# RamaTAV1.net
KiCad netlist of a schematic drawn in EAGLE
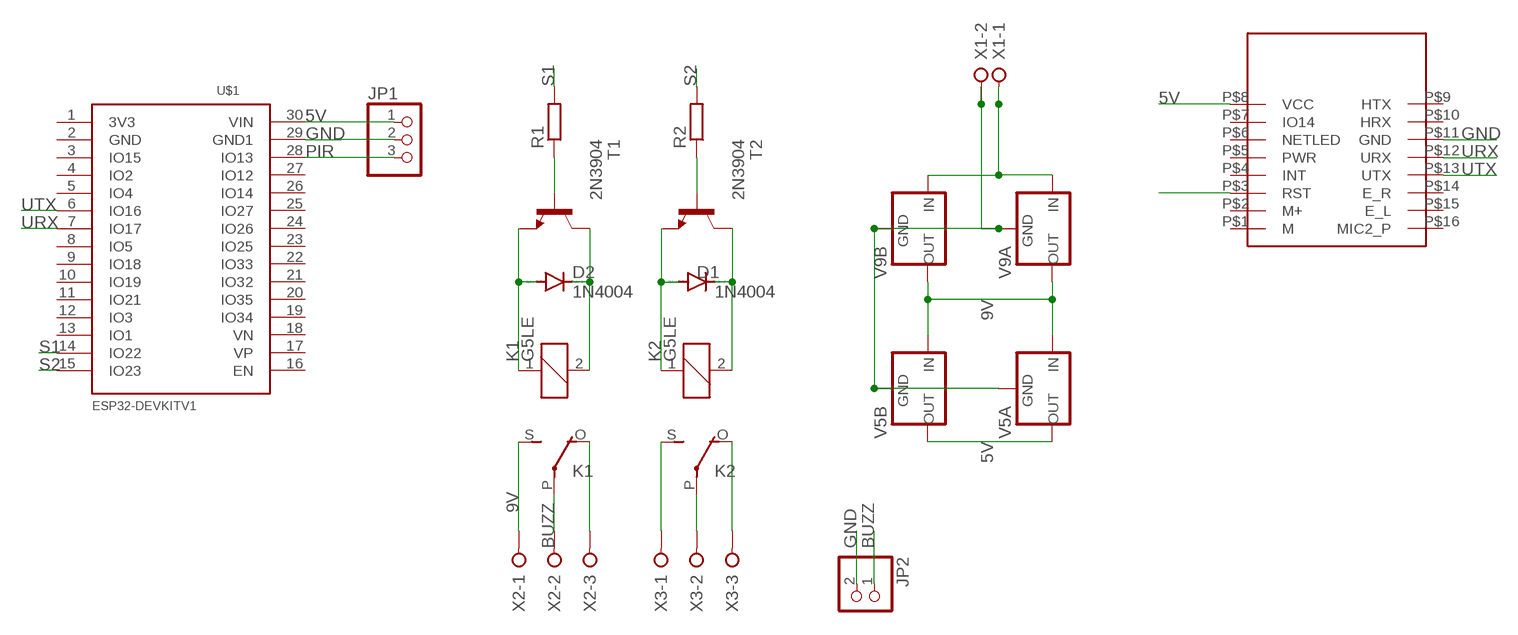
[diagram p0: schematic, sheet 1]

(export (version "E")
  (design (tool "Eeschema 10.0.6"))
  (components
    (comp (ref "D1")
      (value "1N4004")
      (footprint "eagle-import:DO41-10")
      (libsource (lib "eagle-import") (part "1N4004"))
    )
    (comp (ref "D2")
      (value "1N4004")
      (footprint "eagle-import:DO41-10")
      (libsource (lib "eagle-import") (part "1N4004"))
    )
    (comp (ref "JP1")
      (value "PINHD-1X3")
      (footprint "eagle-import:1X03")
      (libsource (lib "eagle-import") (part "PINHD-1X3"))
    )
    (comp (ref "JP2")
      (value "PINHD-1X2")
      (footprint "eagle-import:1X02")
      (libsource (lib "eagle-import") (part "PINHD-1X2"))
    )
    (comp (ref "K1")
      (value "G5LE")
      (footprint "eagle-import:G5LE")
      (libsource (lib "eagle-import") (part "G5LE"))
    )
    (comp (ref "K2")
      (value "G5LE")
      (footprint "eagle-import:G5LE")
      (libsource (lib "eagle-import") (part "G5LE"))
    )
    (comp (ref "R1")
      (value "R-EU_0207/10")
      (footprint "eagle-import:0207_10")
      (libsource (lib "eagle-import") (part "R-EU_0207/10"))
    )
    (comp (ref "R2")
      (value "R-EU_0207/10")
      (footprint "eagle-import:0207_10")
      (libsource (lib "eagle-import") (part "R-EU_0207/10"))
    )
    (comp (ref "T1")
      (value "2N3904")
      (footprint "eagle-import:TO92")
      (libsource (lib "eagle-import") (part "2N3904"))
    )
    (comp (ref "T2")
      (value "2N3904")
      (footprint "eagle-import:TO92")
      (libsource (lib "eagle-import") (part "2N3904"))
    )
    (comp (ref "U$1")
      (value "ESP32DEVKITV1")
      (footprint "eagle-import:ESP32-DEVKITV1")
      (libsource (lib "eagle-import") (part "ESP32DEVKITV1"))
    )
    (comp (ref "U$7")
      (value "SIM_A6SIM_GA6")
      (footprint "eagle-import:SIM_GA6")
      (libsource (lib "eagle-import") (part "SIM_A6SIM_GA6"))
    )
    (comp (ref "V5A")
      (value "78XXS")
      (footprint "eagle-import:78XXS")
      (libsource (lib "eagle-import") (part "78XXS"))
    )
    (comp (ref "V5B")
      (value "78XXS")
      (footprint "eagle-import:78XXS")
      (libsource (lib "eagle-import") (part "78XXS"))
    )
    (comp (ref "V9A")
      (value "78XXS")
      (footprint "eagle-import:78XXS")
      (libsource (lib "eagle-import") (part "78XXS"))
    )
    (comp (ref "V9B")
      (value "78XXS")
      (footprint "eagle-import:78XXS")
      (libsource (lib "eagle-import") (part "78XXS"))
    )
    (comp (ref "X1")
      (value "W237-02P")
      (footprint "eagle-import:W237-2")
      (libsource (lib "eagle-import") (part "W237-02P"))
    )
    (comp (ref "X2")
      (value "W237-03P")
      (footprint "eagle-import:W237-3")
      (libsource (lib "eagle-import") (part "W237-03P"))
    )
    (comp (ref "X3")
      (value "W237-03P")
      (footprint "eagle-import:W237-3")
      (libsource (lib "eagle-import") (part "W237-03P"))
    )
  )
  (nets
    (net (code "1") (name "/5V") (class "Default")
      (node (ref "JP1") (pin "1") (pinfunction "1_1") (pintype "passive"))
      (node (ref "U$1") (pin "30") (pinfunction "VIN_30") (pintype "bidirectional"))
      (node (ref "U$7") (pin "P$8") (pinfunction "VCC_P$8") (pintype "bidirectional"))
      (node (ref "V5A") (pin "OUT") (pinfunction "OUT_OUT") (pintype "passive"))
      (node (ref "V5B") (pin "OUT") (pinfunction "OUT_OUT") (pintype "passive"))
    )
    (net (code "2") (name "/9V") (class "Default")
      (node (ref "K1") (pin "S") (pinfunction "S_S") (pintype "passive"))
      (node (ref "V5A") (pin "IN") (pinfunction "IN_IN") (pintype "input"))
      (node (ref "V5B") (pin "IN") (pinfunction "IN_IN") (pintype "input"))
      (node (ref "V9A") (pin "OUT") (pinfunction "OUT_OUT") (pintype "passive"))
      (node (ref "V9B") (pin "OUT") (pinfunction "OUT_OUT") (pintype "passive"))
      (node (ref "X2") (pin "1") (pinfunction "KL_1") (pintype "passive"))
    )
    (net (code "3") (name "/BUZZ") (class "Default")
      (node (ref "JP2") (pin "1") (pinfunction "1_1") (pintype "passive"))
      (node (ref "K1") (pin "P") (pinfunction "P_P") (pintype "passive"))
      (node (ref "X2") (pin "2") (pinfunction "KL_2") (pintype "passive"))
    )
    (net (code "4") (name "/GND") (class "Default")
      (node (ref "JP1") (pin "2") (pinfunction "2_2") (pintype "passive"))
      (node (ref "JP2") (pin "2") (pinfunction "2_2") (pintype "passive"))
      (node (ref "U$1") (pin "29") (pinfunction "GND1_29") (pintype "bidirectional"))
      (node (ref "U$7") (pin "P$11") (pinfunction "GND_P$11") (pintype "bidirectional"))
    )
    (net (code "5") (name "/PIR") (class "Default")
      (node (ref "JP1") (pin "3") (pinfunction "3_3") (pintype "passive"))
      (node (ref "U$1") (pin "28") (pinfunction "IO13_28") (pintype "bidirectional"))
    )
    (net (code "6") (name "/S1") (class "Default")
      (node (ref "R1") (pin "2") (pinfunction "2_2") (pintype "passive"))
      (node (ref "U$1") (pin "14") (pinfunction "IO22_14") (pintype "bidirectional"))
    )
    (net (code "7") (name "/S2") (class "Default")
      (node (ref "R2") (pin "2") (pinfunction "2_2") (pintype "passive"))
      (node (ref "U$1") (pin "15") (pinfunction "IO23_15") (pintype "bidirectional"))
    )
    (net (code "8") (name "/URX") (class "Default")
      (node (ref "U$1") (pin "7") (pinfunction "IO17_7") (pintype "bidirectional"))
      (node (ref "U$7") (pin "P$12") (pinfunction "URX_P$12") (pintype "bidirectional"))
    )
    (net (code "9") (name "/UTX") (class "Default")
      (node (ref "U$1") (pin "6") (pinfunction "IO16_6") (pintype "bidirectional"))
      (node (ref "U$7") (pin "P$13") (pinfunction "UTX_P$13") (pintype "bidirectional"))
    )
    (net (code "10") (name "Net-(T1-B)") (class "Default")
      (node (ref "R1") (pin "1") (pinfunction "1_1") (pintype "passive"))
      (node (ref "T1") (pin "2") (pinfunction "B_2") (pintype "passive"))
    )
    (net (code "11") (name "Net-(T1-C)") (class "Default")
      (node (ref "D2") (pin "C") (pinfunction "C_C") (pintype "passive"))
      (node (ref "K1") (pin "2") (pinfunction "2_2") (pintype "passive"))
      (node (ref "T1") (pin "1") (pinfunction "C_1") (pintype "passive"))
    )
    (net (code "12") (name "Net-(T1-E)") (class "Default")
      (node (ref "D2") (pin "A") (pinfunction "A_A") (pintype "passive"))
      (node (ref "K1") (pin "1") (pinfunction "1_1") (pintype "passive"))
      (node (ref "T1") (pin "3") (pinfunction "E_3") (pintype "passive"))
    )
    (net (code "13") (name "Net-(T2-B)") (class "Default")
      (node (ref "R2") (pin "1") (pinfunction "1_1") (pintype "passive"))
      (node (ref "T2") (pin "2") (pinfunction "B_2") (pintype "passive"))
    )
    (net (code "14") (name "Net-(T2-C)") (class "Default")
      (node (ref "D1") (pin "C") (pinfunction "C_C") (pintype "passive"))
      (node (ref "K2") (pin "2") (pinfunction "2_2") (pintype "passive"))
      (node (ref "T2") (pin "1") (pinfunction "C_1") (pintype "passive"))
    )
    (net (code "15") (name "Net-(T2-E)") (class "Default")
      (node (ref "D1") (pin "A") (pinfunction "A_A") (pintype "passive"))
      (node (ref "K2") (pin "1") (pinfunction "1_1") (pintype "passive"))
      (node (ref "T2") (pin "3") (pinfunction "E_3") (pintype "passive"))
    )
    (net (code "16") (name "Net-(X1A-KL)") (class "Default")
      (node (ref "V9A") (pin "IN") (pinfunction "IN_IN") (pintype "input"))
      (node (ref "V9B") (pin "IN") (pinfunction "IN_IN") (pintype "input"))
      (node (ref "X1") (pin "1") (pinfunction "KL_1") (pintype "passive"))
    )
    (net (code "17") (name "Net-(X1B-KL)") (class "Default")
      (node (ref "V5A") (pin "GND") (pinfunction "GND_GND") (pintype "input"))
      (node (ref "V5B") (pin "GND") (pinfunction "GND_GND") (pintype "input"))
      (node (ref "V9A") (pin "GND") (pinfunction "GND_GND") (pintype "input"))
      (node (ref "V9B") (pin "GND") (pinfunction "GND_GND") (pintype "input"))
      (node (ref "X1") (pin "2") (pinfunction "KL_2") (pintype "passive"))
    )
    (net (code "18") (name "Net-(X2C-KL)") (class "Default")
      (node (ref "K1") (pin "O") (pinfunction "O_O") (pintype "passive"))
      (node (ref "X2") (pin "3") (pinfunction "KL_3") (pintype "passive"))
    )
    (net (code "19") (name "Net-(X3A-KL)") (class "Default")
      (node (ref "K2") (pin "S") (pinfunction "S_S") (pintype "passive"))
      (node (ref "X3") (pin "1") (pinfunction "KL_1") (pintype "passive"))
    )
    (net (code "20") (name "Net-(X3B-KL)") (class "Default")
      (node (ref "K2") (pin "P") (pinfunction "P_P") (pintype "passive"))
      (node (ref "X3") (pin "2") (pinfunction "KL_2") (pintype "passive"))
    )
    (net (code "21") (name "Net-(X3C-KL)") (class "Default")
      (node (ref "K2") (pin "O") (pinfunction "O_O") (pintype "passive"))
      (node (ref "X3") (pin "3") (pinfunction "KL_3") (pintype "passive"))
    )
    (net (code "22") (name "unconnected-(U$1-3V3-Pad1)") (class "Default")
      (node (ref "U$1") (pin "1") (pinfunction "3V3_1") (pintype "bidirectional"))
    )
    (net (code "23") (name "unconnected-(U$1-EN-Pad16)") (class "Default")
      (node (ref "U$1") (pin "16") (pinfunction "EN_16") (pintype "bidirectional"))
    )
    (net (code "24") (name "unconnected-(U$1-GND-Pad2)") (class "Default")
      (node (ref "U$1") (pin "2") (pinfunction "GND_2") (pintype "bidirectional"))
    )
    (net (code "25") (name "unconnected-(U$1-IO1-Pad13)") (class "Default")
      (node (ref "U$1") (pin "13") (pinfunction "IO1_13") (pintype "bidirectional"))
    )
    (net (code "26") (name "unconnected-(U$1-IO2-Pad4)") (class "Default")
      (node (ref "U$1") (pin "4") (pinfunction "IO2_4") (pintype "bidirectional"))
    )
    (net (code "27") (name "unconnected-(U$1-IO3-Pad12)") (class "Default")
      (node (ref "U$1") (pin "12") (pinfunction "IO3_12") (pintype "bidirectional"))
    )
    (net (code "28") (name "unconnected-(U$1-IO4-Pad5)") (class "Default")
      (node (ref "U$1") (pin "5") (pinfunction "IO4_5") (pintype "bidirectional"))
    )
    (net (code "29") (name "unconnected-(U$1-IO5-Pad8)") (class "Default")
      (node (ref "U$1") (pin "8") (pinfunction "IO5_8") (pintype "bidirectional"))
    )
    (net (code "30") (name "unconnected-(U$1-IO12-Pad27)") (class "Default")
      (node (ref "U$1") (pin "27") (pinfunction "IO12_27") (pintype "bidirectional"))
    )
    (net (code "31") (name "unconnected-(U$1-IO14-Pad26)") (class "Default")
      (node (ref "U$1") (pin "26") (pinfunction "IO14_26") (pintype "bidirectional"))
    )
    (net (code "32") (name "unconnected-(U$1-IO15-Pad3)") (class "Default")
      (node (ref "U$1") (pin "3") (pinfunction "IO15_3") (pintype "bidirectional"))
    )
    (net (code "33") (name "unconnected-(U$1-IO18-Pad9)") (class "Default")
      (node (ref "U$1") (pin "9") (pinfunction "IO18_9") (pintype "bidirectional"))
    )
    (net (code "34") (name "unconnected-(U$1-IO19-Pad10)") (class "Default")
      (node (ref "U$1") (pin "10") (pinfunction "IO19_10") (pintype "bidirectional"))
    )
    (net (code "35") (name "unconnected-(U$1-IO21-Pad11)") (class "Default")
      (node (ref "U$1") (pin "11") (pinfunction "IO21_11") (pintype "bidirectional"))
    )
    (net (code "36") (name "unconnected-(U$1-IO25-Pad23)") (class "Default")
      (node (ref "U$1") (pin "23") (pinfunction "IO25_23") (pintype "bidirectional"))
    )
    (net (code "37") (name "unconnected-(U$1-IO26-Pad24)") (class "Default")
      (node (ref "U$1") (pin "24") (pinfunction "IO26_24") (pintype "bidirectional"))
    )
    (net (code "38") (name "unconnected-(U$1-IO27-Pad25)") (class "Default")
      (node (ref "U$1") (pin "25") (pinfunction "IO27_25") (pintype "bidirectional"))
    )
    (net (code "39") (name "unconnected-(U$1-IO32-Pad21)") (class "Default")
      (node (ref "U$1") (pin "21") (pinfunction "IO32_21") (pintype "bidirectional"))
    )
    (net (code "40") (name "unconnected-(U$1-IO33-Pad22)") (class "Default")
      (node (ref "U$1") (pin "22") (pinfunction "IO33_22") (pintype "bidirectional"))
    )
    (net (code "41") (name "unconnected-(U$1-IO34-Pad19)") (class "Default")
      (node (ref "U$1") (pin "19") (pinfunction "IO34_19") (pintype "bidirectional"))
    )
    (net (code "42") (name "unconnected-(U$1-IO35-Pad20)") (class "Default")
      (node (ref "U$1") (pin "20") (pinfunction "IO35_20") (pintype "bidirectional"))
    )
    (net (code "43") (name "unconnected-(U$1-VN-Pad18)") (class "Default")
      (node (ref "U$1") (pin "18") (pinfunction "VN_18") (pintype "bidirectional"))
    )
    (net (code "44") (name "unconnected-(U$1-VP-Pad17)") (class "Default")
      (node (ref "U$1") (pin "17") (pinfunction "VP_17") (pintype "bidirectional"))
    )
    (net (code "45") (name "unconnected-(U$7-E_L-PadP$15)") (class "Default")
      (node (ref "U$7") (pin "P$15") (pinfunction "E_L_P$15") (pintype "bidirectional"))
    )
    (net (code "46") (name "unconnected-(U$7-E_R-PadP$14)") (class "Default")
      (node (ref "U$7") (pin "P$14") (pinfunction "E_R_P$14") (pintype "bidirectional"))
    )
    (net (code "47") (name "unconnected-(U$7-HRX-PadP$10)") (class "Default")
      (node (ref "U$7") (pin "P$10") (pinfunction "HRX_P$10") (pintype "bidirectional"))
    )
    (net (code "48") (name "unconnected-(U$7-HTX-PadP$9)") (class "Default")
      (node (ref "U$7") (pin "P$9") (pinfunction "HTX_P$9") (pintype "bidirectional"))
    )
    (net (code "49") (name "unconnected-(U$7-INT-PadP$4)") (class "Default")
      (node (ref "U$7") (pin "P$4") (pinfunction "INT_P$4") (pintype "bidirectional"))
    )
    (net (code "50") (name "unconnected-(U$7-IO14-PadP$7)") (class "Default")
      (node (ref "U$7") (pin "P$7") (pinfunction "IO14_P$7") (pintype "bidirectional"))
    )
    (net (code "51") (name "unconnected-(U$7-M+-PadP$2)") (class "Default")
      (node (ref "U$7") (pin "P$2") (pinfunction "M+_P$2") (pintype "bidirectional"))
    )
    (net (code "52") (name "unconnected-(U$7-M-PadP$1)") (class "Default")
      (node (ref "U$7") (pin "P$1") (pinfunction "M_P$1") (pintype "bidirectional"))
    )
    (net (code "53") (name "unconnected-(U$7-MIC2_P-PadP$16)") (class "Default")
      (node (ref "U$7") (pin "P$16") (pinfunction "MIC2_P_P$16") (pintype "bidirectional"))
    )
    (net (code "54") (name "unconnected-(U$7-NETLED-PadP$6)") (class "Default")
      (node (ref "U$7") (pin "P$6") (pinfunction "NETLED_P$6") (pintype "bidirectional"))
    )
    (net (code "55") (name "unconnected-(U$7-PWR-PadP$5)") (class "Default")
      (node (ref "U$7") (pin "P$5") (pinfunction "PWR_P$5") (pintype "bidirectional"))
    )
    (net (code "56") (name "unconnected-(U$7-RST-PadP$3)") (class "Default")
      (node (ref "U$7") (pin "P$3") (pinfunction "RST_P$3") (pintype "bidirectional"))
    )
  )
)
